# Raspberry_Pi_inputs.net
KiCad netlist of a schematic drawn in Altium Designer
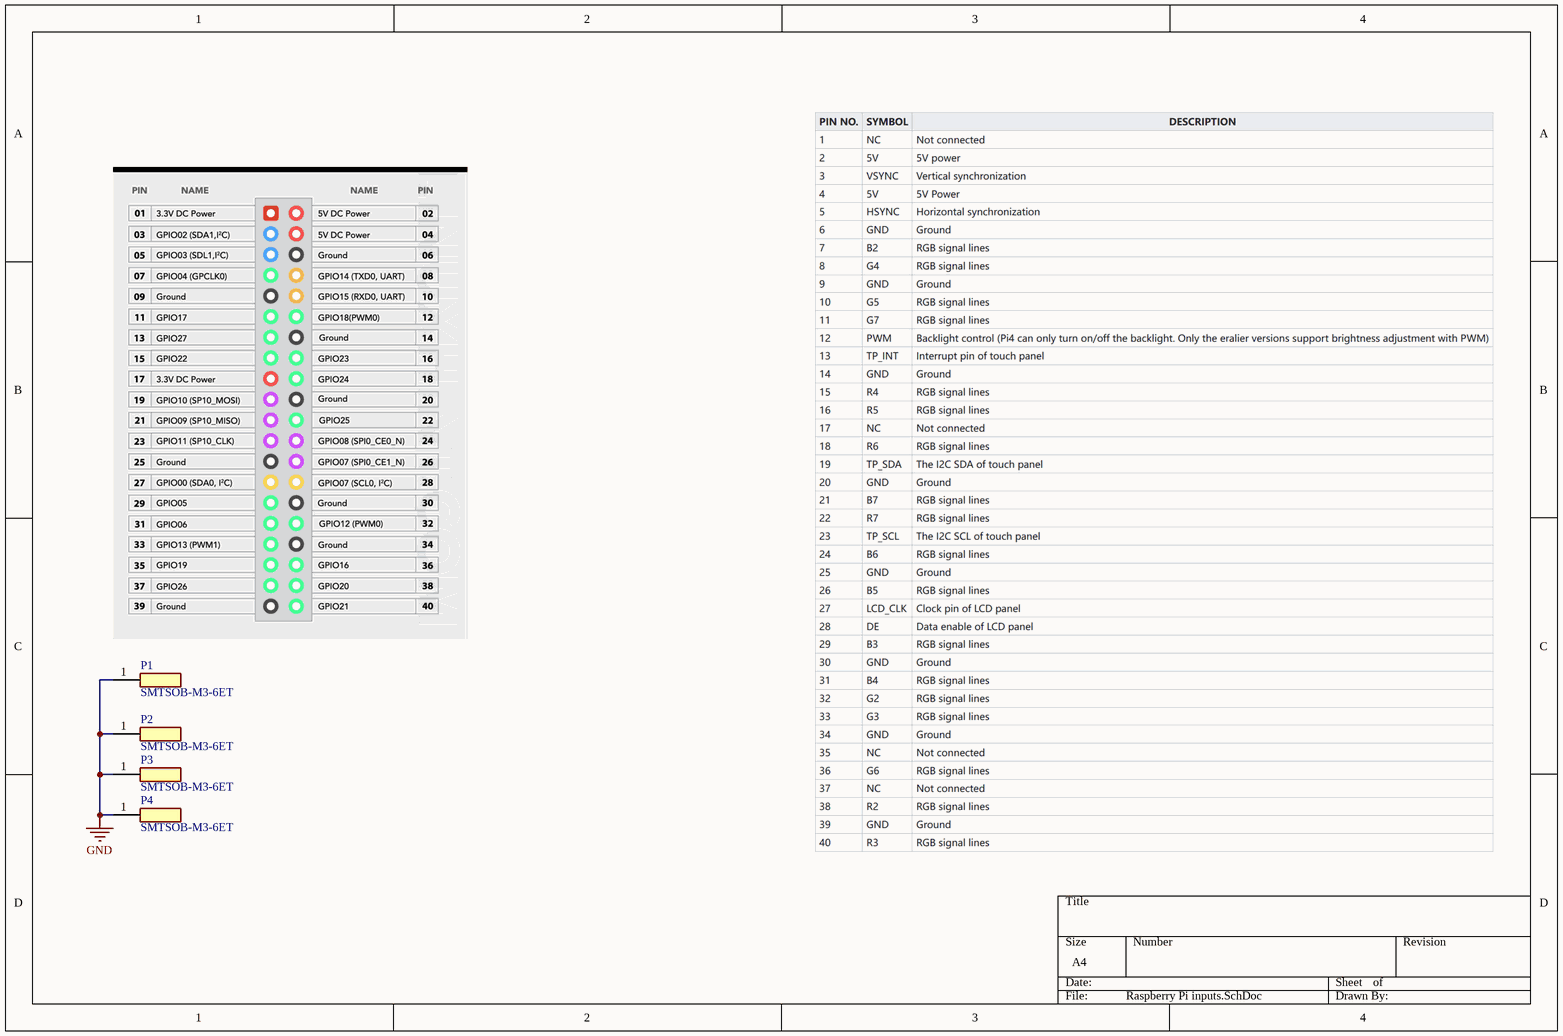
[diagram p0: Raspberry Pi inputs.SchDoc]

(export (version "E")
  (design (tool "Eeschema 10.0.6"))
  (components
    (comp (ref "P1")
      (value "SMTSOB-M3-6ET")
      (footprint "PcbLib:SMTSOB-M3-6ET")
      (description "Spacer 8mm")
      (libsource (lib "Schlib") (part "SMTSOB-M3-6ET"))
    )
    (comp (ref "P2")
      (value "SMTSOB-M3-6ET")
      (footprint "PcbLib:SMTSOB-M3-6ET")
      (description "Spacer 8mm")
      (libsource (lib "Schlib") (part "SMTSOB-M3-6ET"))
    )
    (comp (ref "P3")
      (value "SMTSOB-M3-6ET")
      (footprint "PcbLib:SMTSOB-M3-6ET")
      (description "Spacer 8mm")
      (libsource (lib "Schlib") (part "SMTSOB-M3-6ET"))
    )
    (comp (ref "P4")
      (value "SMTSOB-M3-6ET")
      (footprint "PcbLib:SMTSOB-M3-6ET")
      (description "Spacer 8mm")
      (libsource (lib "Schlib") (part "SMTSOB-M3-6ET"))
    )
  )
  (nets
    (net (code "1") (name "GND") (class "Default")
      (node (ref "P1") (pin "1") (pinfunction "1_1") (pintype "passive"))
      (node (ref "P2") (pin "1") (pinfunction "1_1") (pintype "passive"))
      (node (ref "P3") (pin "1") (pinfunction "1_1") (pintype "passive"))
      (node (ref "P4") (pin "1") (pinfunction "1_1") (pintype "passive"))
    )
  )
)
